# T_1500_C.net
KiCad netlist of a schematic drawn in Altium Designer
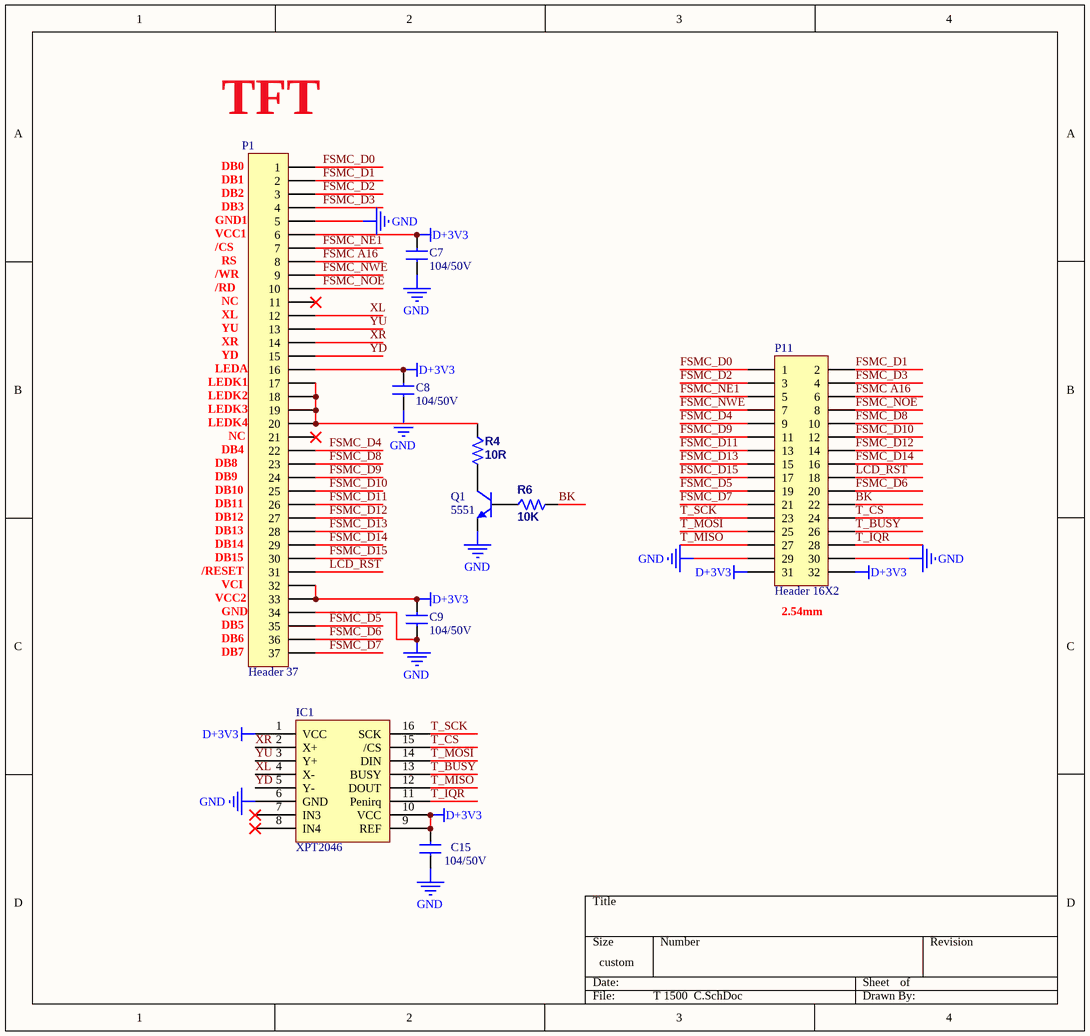
[diagram p0: T 1500  C.SchDoc]

(export (version "E")
  (design (tool "Eeschema 10.0.6"))
  (components
    (comp (ref "C7")
      (value "104/50V")
      (footprint "SMD_RC:C0805")
      (description "无极性电容器")
      (libsource (lib "LANNGE") (part "CAP"))
    )
    (comp (ref "C8")
      (value "104/50V")
      (footprint "SMD_RC:C0805")
      (description "无极性电容器")
      (libsource (lib "LANNGE") (part "CAP"))
    )
    (comp (ref "C9")
      (value "104/50V")
      (footprint "SMD_RC:C0805")
      (description "无极性电容器")
      (libsource (lib "LANNGE") (part "CAP"))
    )
    (comp (ref "C15")
      (value "104/50V")
      (footprint "SMD_RC:C0805")
      (description "无极性电容器")
      (libsource (lib "LANNGE") (part "CAP"))
    )
    (comp (ref "IC1")
      (value "XPT2046")
      (footprint "K3600:SOT403-1_L")
      (libsource (lib "Tiky") (part "ADS7843"))
    )
    (comp (ref "P1")
      (value "Header 37")
      (footprint "HDR1X30")
      (description "Header, 30-Pin")
      (fields (field (name "PUBLISHER") "Altium Limited"))
      (libsource (lib "LANNGE_TEMP") (part "Header 37"))
    )
    (comp (ref "P11")
      (value "Header 16X2")
      (footprint "HDR2X16")
      (description "Header, 16-Pin, Dual row")
      (fields (field (name "PUBLISHER") "Altium Limited"))
      (libsource (lib "Miscellaneous Connectors") (part "Header 16X2"))
    )
    (comp (ref "Q1")
      (value "5551")
      (footprint "SOT-23")
      (description "NPN(160V/0.6A/0.6W/100MHz/E.B.C)")
      (fields (field (name "PUBLISHER") "Altium Limited"))
      (libsource (lib "LANNGE") (part "2N5551"))
    )
    (comp (ref "R4") (value "10R") (footprint "R0603") (libsource (lib "*") (part "RES2-S")))
    (comp (ref "R6") (value "10K") (footprint "R0603") (libsource (lib "*") (part "RES2-S")))
  )
  (nets
    (net (code "1") (name "/BK") (class "Default")
      (node (ref "P11") (pin "22") (pinfunction "22_22") (pintype "passive"))
      (node (ref "R6") (pin "2") (pintype "passive"))
    )
    (net (code "2") (name "/FSMC A16") (class "Default")
      (node (ref "P1") (pin "8") (pinfunction "8_8") (pintype "passive"))
      (node (ref "P11") (pin "6") (pinfunction "6_6") (pintype "passive"))
    )
    (net (code "3") (name "/FSMC_D0") (class "Default")
      (node (ref "P1") (pin "1") (pinfunction "1_1") (pintype "passive"))
      (node (ref "P11") (pin "1") (pinfunction "1_1") (pintype "passive"))
    )
    (net (code "4") (name "/FSMC_D1") (class "Default")
      (node (ref "P1") (pin "2") (pinfunction "2_2") (pintype "passive"))
      (node (ref "P11") (pin "2") (pinfunction "2_2") (pintype "passive"))
    )
    (net (code "5") (name "/FSMC_D2") (class "Default")
      (node (ref "P1") (pin "3") (pinfunction "3_3") (pintype "passive"))
      (node (ref "P11") (pin "3") (pinfunction "3_3") (pintype "passive"))
    )
    (net (code "6") (name "/FSMC_D3") (class "Default")
      (node (ref "P1") (pin "4") (pinfunction "4_4") (pintype "passive"))
      (node (ref "P11") (pin "4") (pinfunction "4_4") (pintype "passive"))
    )
    (net (code "7") (name "/FSMC_D4") (class "Default")
      (node (ref "P1") (pin "22") (pinfunction "22_22") (pintype "passive"))
      (node (ref "P11") (pin "9") (pinfunction "9_9") (pintype "passive"))
    )
    (net (code "8") (name "/FSMC_D5") (class "Default")
      (node (ref "P1") (pin "35") (pinfunction "35_35") (pintype "passive"))
      (node (ref "P11") (pin "19") (pinfunction "19_19") (pintype "passive"))
    )
    (net (code "9") (name "/FSMC_D6") (class "Default")
      (node (ref "P1") (pin "36") (pinfunction "36_36") (pintype "passive"))
      (node (ref "P11") (pin "20") (pinfunction "20_20") (pintype "passive"))
    )
    (net (code "10") (name "/FSMC_D7") (class "Default")
      (node (ref "P1") (pin "37") (pinfunction "37_37") (pintype "passive"))
      (node (ref "P11") (pin "21") (pinfunction "21_21") (pintype "passive"))
    )
    (net (code "11") (name "/FSMC_D8") (class "Default")
      (node (ref "P1") (pin "23") (pinfunction "23_23") (pintype "passive"))
      (node (ref "P11") (pin "10") (pinfunction "10_10") (pintype "passive"))
    )
    (net (code "12") (name "/FSMC_D9") (class "Default")
      (node (ref "P1") (pin "24") (pinfunction "24_24") (pintype "passive"))
      (node (ref "P11") (pin "11") (pinfunction "11_11") (pintype "passive"))
    )
    (net (code "13") (name "/FSMC_D10") (class "Default")
      (node (ref "P1") (pin "25") (pinfunction "25_25") (pintype "passive"))
      (node (ref "P11") (pin "12") (pinfunction "12_12") (pintype "passive"))
    )
    (net (code "14") (name "/FSMC_D11") (class "Default")
      (node (ref "P1") (pin "26") (pinfunction "26_26") (pintype "passive"))
      (node (ref "P11") (pin "13") (pinfunction "13_13") (pintype "passive"))
    )
    (net (code "15") (name "/FSMC_D12") (class "Default")
      (node (ref "P1") (pin "27") (pinfunction "27_27") (pintype "passive"))
      (node (ref "P11") (pin "14") (pinfunction "14_14") (pintype "passive"))
    )
    (net (code "16") (name "/FSMC_D13") (class "Default")
      (node (ref "P1") (pin "28") (pinfunction "28_28") (pintype "passive"))
      (node (ref "P11") (pin "15") (pinfunction "15_15") (pintype "passive"))
    )
    (net (code "17") (name "/FSMC_D14") (class "Default")
      (node (ref "P1") (pin "29") (pinfunction "29_29") (pintype "passive"))
      (node (ref "P11") (pin "16") (pinfunction "16_16") (pintype "passive"))
    )
    (net (code "18") (name "/FSMC_D15") (class "Default")
      (node (ref "P1") (pin "30") (pinfunction "30_30") (pintype "passive"))
      (node (ref "P11") (pin "17") (pinfunction "17_17") (pintype "passive"))
    )
    (net (code "19") (name "/FSMC_NE1") (class "Default")
      (node (ref "P1") (pin "7") (pinfunction "7_7") (pintype "passive"))
      (node (ref "P11") (pin "5") (pinfunction "5_5") (pintype "passive"))
    )
    (net (code "20") (name "/FSMC_NOE") (class "Default")
      (node (ref "P1") (pin "10") (pinfunction "10_10") (pintype "passive"))
      (node (ref "P11") (pin "8") (pinfunction "8_8") (pintype "passive"))
    )
    (net (code "21") (name "/FSMC_NWE") (class "Default")
      (node (ref "P1") (pin "9") (pinfunction "9_9") (pintype "passive"))
      (node (ref "P11") (pin "7") (pinfunction "7_7") (pintype "passive"))
    )
    (net (code "22") (name "/LCD_RST") (class "Default")
      (node (ref "P1") (pin "31") (pinfunction "31_31") (pintype "passive"))
      (node (ref "P11") (pin "18") (pinfunction "18_18") (pintype "passive"))
    )
    (net (code "23") (name "/T_BUSY") (class "Default")
      (node (ref "IC1") (pin "13") (pinfunction "BUSY_13") (pintype "passive"))
      (node (ref "P11") (pin "26") (pinfunction "26_26") (pintype "passive"))
    )
    (net (code "24") (name "/T_CS") (class "Default")
      (node (ref "IC1") (pin "15") (pinfunction "/CS_15") (pintype "passive"))
      (node (ref "P11") (pin "24") (pinfunction "24_24") (pintype "passive"))
    )
    (net (code "25") (name "/T_IQR") (class "Default")
      (node (ref "IC1") (pin "11") (pinfunction "Penirq_11") (pintype "passive"))
      (node (ref "P11") (pin "28") (pinfunction "28_28") (pintype "passive"))
    )
    (net (code "26") (name "/T_MISO") (class "Default")
      (node (ref "IC1") (pin "12") (pinfunction "DOUT_12") (pintype "passive"))
      (node (ref "P11") (pin "27") (pinfunction "27_27") (pintype "passive"))
    )
    (net (code "27") (name "/T_MOSI") (class "Default")
      (node (ref "IC1") (pin "14") (pinfunction "DIN_14") (pintype "passive"))
      (node (ref "P11") (pin "25") (pinfunction "25_25") (pintype "passive"))
    )
    (net (code "28") (name "/T_SCK") (class "Default")
      (node (ref "IC1") (pin "16") (pinfunction "SCK_16") (pintype "passive"))
      (node (ref "P11") (pin "23") (pinfunction "23_23") (pintype "passive"))
    )
    (net (code "29") (name "/XL") (class "Default")
      (node (ref "IC1") (pin "4") (pinfunction "X-_4") (pintype "passive"))
      (node (ref "P1") (pin "12") (pinfunction "12_12") (pintype "passive"))
    )
    (net (code "30") (name "/XR") (class "Default")
      (node (ref "IC1") (pin "2") (pinfunction "X+_2") (pintype "passive"))
      (node (ref "P1") (pin "14") (pinfunction "14_14") (pintype "passive"))
    )
    (net (code "31") (name "/YD") (class "Default")
      (node (ref "IC1") (pin "5") (pinfunction "Y-_5") (pintype "passive"))
      (node (ref "P1") (pin "15") (pinfunction "15_15") (pintype "passive"))
    )
    (net (code "32") (name "/YU") (class "Default")
      (node (ref "IC1") (pin "3") (pinfunction "Y+_3") (pintype "passive"))
      (node (ref "P1") (pin "13") (pinfunction "13_13") (pintype "passive"))
    )
    (net (code "33") (name "D+3V3") (class "Default")
      (node (ref "C15") (pin "1") (pinfunction "1_1") (pintype "passive"))
      (node (ref "C7") (pin "1") (pinfunction "1_1") (pintype "passive"))
      (node (ref "C8") (pin "1") (pinfunction "1_1") (pintype "passive"))
      (node (ref "C9") (pin "1") (pinfunction "1_1") (pintype "passive"))
      (node (ref "IC1") (pin "1") (pinfunction "VCC_1") (pintype "passive"))
      (node (ref "IC1") (pin "10") (pinfunction "VCC_10") (pintype "passive"))
      (node (ref "IC1") (pin "9") (pinfunction "REF_9") (pintype "passive"))
      (node (ref "P1") (pin "16") (pinfunction "16_16") (pintype "passive"))
      (node (ref "P1") (pin "32") (pinfunction "32_32") (pintype "passive"))
      (node (ref "P1") (pin "33") (pinfunction "33_33") (pintype "passive"))
      (node (ref "P1") (pin "6") (pinfunction "6_6") (pintype "passive"))
      (node (ref "P11") (pin "31") (pinfunction "31_31") (pintype "passive"))
      (node (ref "P11") (pin "32") (pinfunction "32_32") (pintype "passive"))
    )
    (net (code "34") (name "GND") (class "Default")
      (node (ref "C15") (pin "2") (pinfunction "2_2") (pintype "passive"))
      (node (ref "C7") (pin "2") (pinfunction "2_2") (pintype "passive"))
      (node (ref "C8") (pin "2") (pinfunction "2_2") (pintype "passive"))
      (node (ref "C9") (pin "2") (pinfunction "2_2") (pintype "passive"))
      (node (ref "IC1") (pin "6") (pinfunction "GND_6") (pintype "passive"))
      (node (ref "P1") (pin "34") (pinfunction "34_34") (pintype "passive"))
      (node (ref "P1") (pin "5") (pinfunction "5_5") (pintype "passive"))
      (node (ref "P11") (pin "29") (pinfunction "29_29") (pintype "passive"))
      (node (ref "P11") (pin "30") (pinfunction "30_30") (pintype "passive"))
      (node (ref "Q1") (pin "2") (pinfunction "E_2") (pintype "passive"))
    )
    (net (code "35") (name "Net-(P1-Pad17)") (class "Default")
      (node (ref "P1") (pin "17") (pinfunction "17_17") (pintype "passive"))
      (node (ref "P1") (pin "18") (pinfunction "18_18") (pintype "passive"))
      (node (ref "P1") (pin "19") (pinfunction "19_19") (pintype "passive"))
      (node (ref "P1") (pin "20") (pinfunction "20_20") (pintype "passive"))
      (node (ref "R4") (pin "1") (pintype "passive"))
    )
    (net (code "36") (name "Net-(Q1-B)") (class "Default")
      (node (ref "Q1") (pin "1") (pinfunction "B_1") (pintype "passive"))
      (node (ref "R6") (pin "1") (pintype "passive"))
    )
    (net (code "37") (name "Net-(Q1-C)") (class "Default")
      (node (ref "Q1") (pin "3") (pinfunction "C_3") (pintype "passive"))
      (node (ref "R4") (pin "2") (pintype "passive"))
    )
    (net (code "38") (name "unconnected-(IC1-IN3-Pad7)") (class "Default")
      (node (ref "IC1") (pin "7") (pinfunction "IN3_7") (pintype "passive+no_connect"))
    )
    (net (code "39") (name "unconnected-(IC1-IN4-Pad8)") (class "Default")
      (node (ref "IC1") (pin "8") (pinfunction "IN4_8") (pintype "passive+no_connect"))
    )
    (net (code "40") (name "unconnected-(P1-Pad11)") (class "Default")
      (node (ref "P1") (pin "11") (pinfunction "11_11") (pintype "passive+no_connect"))
    )
    (net (code "41") (name "unconnected-(P1-Pad21)") (class "Default")
      (node (ref "P1") (pin "21") (pinfunction "21_21") (pintype "passive+no_connect"))
    )
  )
)
